# studna.net
KiCad netlist of a schematic drawn in EAGLE
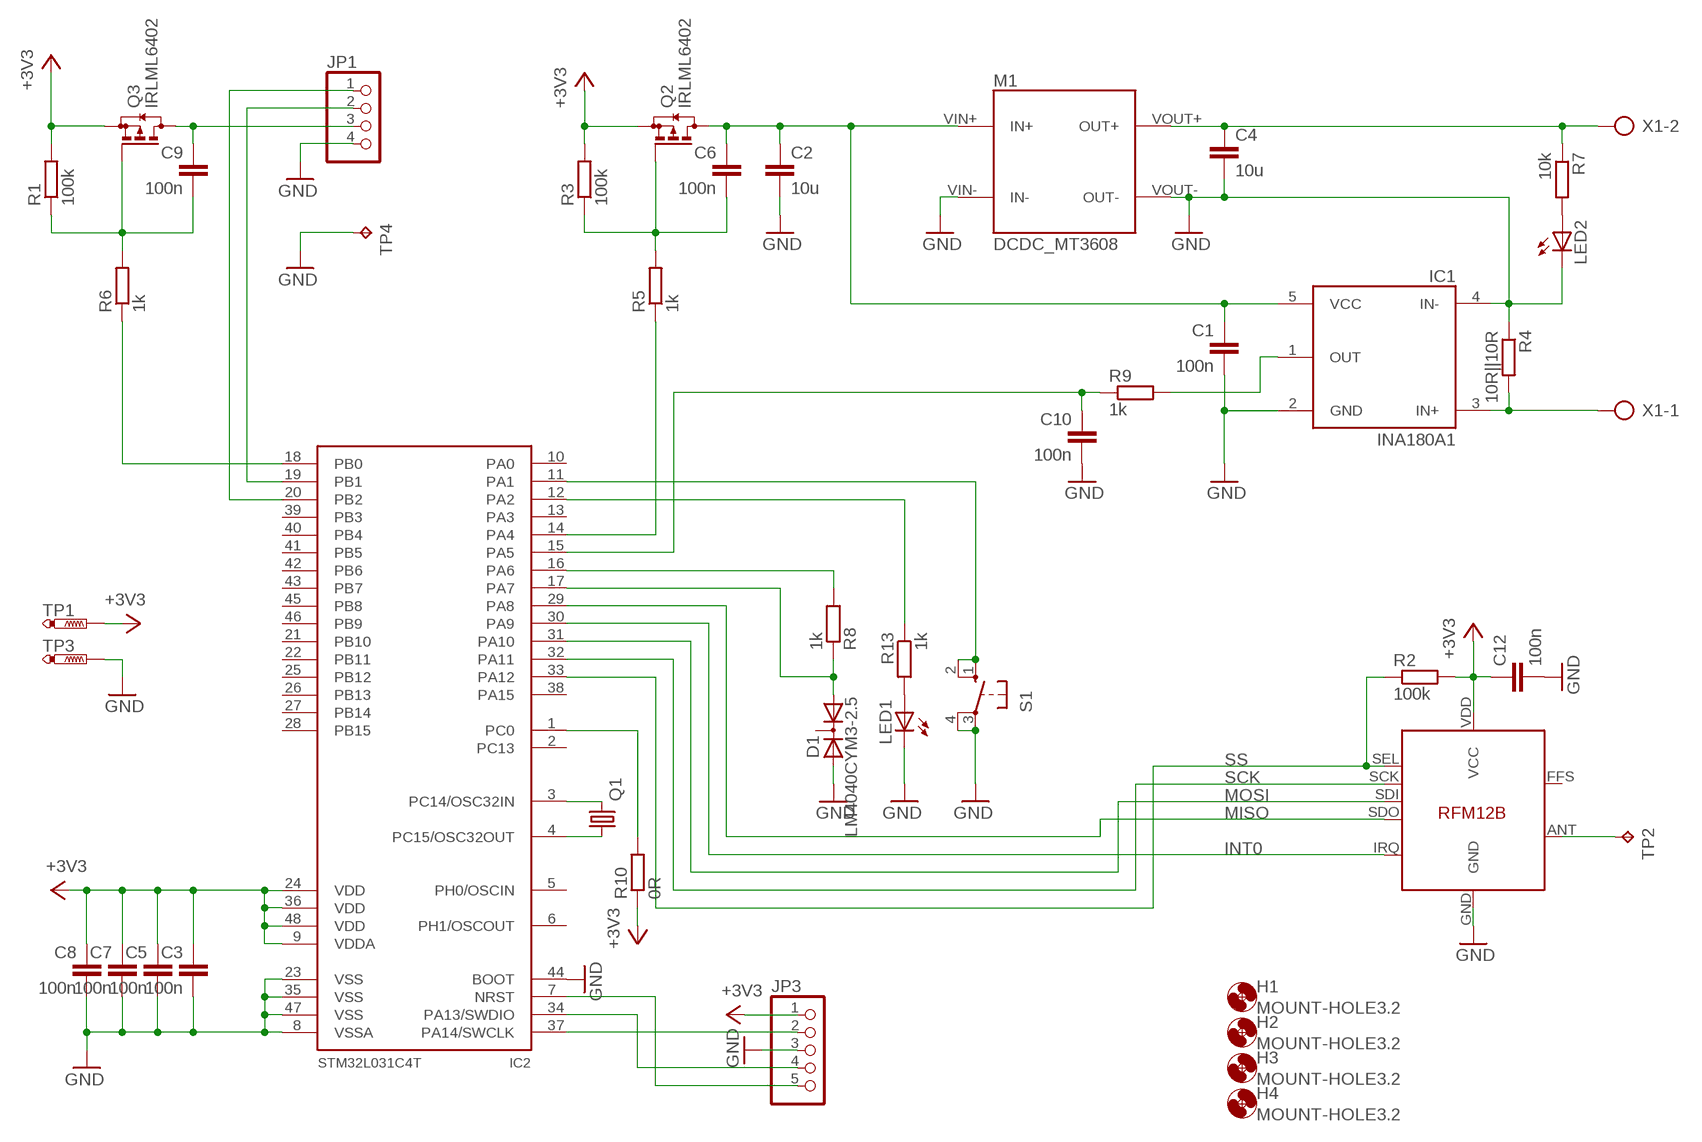
[diagram p0: schematic, sheet 1]

(export (version "E")
  (design (tool "Eeschema 10.0.6"))
  (components
    (comp (ref "C1")
      (value "100n")
      (footprint "eagle-import:C0603")
      (libsource (lib "eagle-import") (part "C-EUC0603"))
    )
    (comp (ref "C2")
      (value "10u")
      (footprint "eagle-import:C1206K")
      (libsource (lib "eagle-import") (part "C-EUC1206K"))
    )
    (comp (ref "C3")
      (value "100n")
      (footprint "eagle-import:C0603")
      (libsource (lib "eagle-import") (part "C-EUC0603"))
    )
    (comp (ref "C4")
      (value "10u")
      (footprint "eagle-import:C1206K")
      (libsource (lib "eagle-import") (part "C-EUC1206K"))
    )
    (comp (ref "C5")
      (value "100n")
      (footprint "eagle-import:C0603")
      (libsource (lib "eagle-import") (part "C-EUC0603"))
    )
    (comp (ref "C6")
      (value "100n")
      (footprint "eagle-import:C0603")
      (libsource (lib "eagle-import") (part "C-EUC0603"))
    )
    (comp (ref "C7")
      (value "100n")
      (footprint "eagle-import:C0603")
      (libsource (lib "eagle-import") (part "C-EUC0603"))
    )
    (comp (ref "C8")
      (value "100n")
      (footprint "eagle-import:C0603")
      (libsource (lib "eagle-import") (part "C-EUC0603"))
    )
    (comp (ref "C9")
      (value "100n")
      (footprint "eagle-import:C0603")
      (libsource (lib "eagle-import") (part "C-EUC0603"))
    )
    (comp (ref "C10")
      (value "100n")
      (footprint "eagle-import:C0603")
      (libsource (lib "eagle-import") (part "C-EUC0603"))
    )
    (comp (ref "C12")
      (value "100n")
      (footprint "eagle-import:C0603")
      (libsource (lib "eagle-import") (part "C-EUC0603"))
    )
    (comp (ref "D1")
      (value "LM4040CYM3-2.5")
      (footprint "eagle-import:SOT23")
      (libsource (lib "eagle-import") (part "DIODE-2AC|CASOT23"))
    )
    (comp (ref "H1")
      (value "MOUNT-HOLE3.2")
      (footprint "eagle-import:3,2")
      (libsource (lib "eagle-import") (part "MOUNT-HOLE3.2"))
    )
    (comp (ref "H2")
      (value "MOUNT-HOLE3.2")
      (footprint "eagle-import:3,2")
      (libsource (lib "eagle-import") (part "MOUNT-HOLE3.2"))
    )
    (comp (ref "H3")
      (value "MOUNT-HOLE3.2")
      (footprint "eagle-import:3,2")
      (libsource (lib "eagle-import") (part "MOUNT-HOLE3.2"))
    )
    (comp (ref "H4")
      (value "MOUNT-HOLE3.2")
      (footprint "eagle-import:3,2")
      (libsource (lib "eagle-import") (part "MOUNT-HOLE3.2"))
    )
    (comp (ref "IC1")
      (value "INA180A1")
      (footprint "eagle-import:SOT23-5L")
      (libsource (lib "eagle-import") (part "INA180"))
    )
    (comp (ref "IC2")
      (value "STM32L031C4T")
      (footprint "eagle-import:LQFP48")
      (libsource (lib "eagle-import") (part "STM32L031C4T"))
    )
    (comp (ref "IC3")
      (value "RFM12B")
      (footprint "eagle-import:RFM12B")
      (libsource (lib "eagle-import") (part "RFM12B"))
    )
    (comp (ref "JP1")
      (value "PINHD-1X4")
      (footprint "eagle-import:1X04")
      (libsource (lib "eagle-import") (part "PINHD-1X4"))
    )
    (comp (ref "JP3")
      (value "PINHD-1X5")
      (footprint "eagle-import:1X05")
      (libsource (lib "eagle-import") (part "PINHD-1X5"))
    )
    (comp (ref "LED1")
      (value "LED3MM")
      (footprint "eagle-import:LED3MM")
      (libsource (lib "eagle-import") (part "LED3MM"))
    )
    (comp (ref "LED2")
      (value "LED3MM")
      (footprint "eagle-import:LED3MM")
      (libsource (lib "eagle-import") (part "LED3MM"))
    )
    (comp (ref "M1")
      (value "DCDC_MT3608")
      (footprint "eagle-import:DCDC_MT3608")
      (libsource (lib "eagle-import") (part "DCDC_MT3608"))
    )
    (comp (ref "Q1")
      (value "CRYSTALTC38H")
      (footprint "eagle-import:TC38H")
      (libsource (lib "eagle-import") (part "CRYSTALTC38H"))
    )
    (comp (ref "Q2")
      (value "IRLML6402")
      (footprint "eagle-import:SOT23")
      (libsource (lib "eagle-import") (part "BSS84"))
    )
    (comp (ref "Q3")
      (value "IRLML6402")
      (footprint "eagle-import:SOT23")
      (libsource (lib "eagle-import") (part "BSS84"))
    )
    (comp (ref "R1")
      (value "100k")
      (footprint "eagle-import:R0603")
      (libsource (lib "eagle-import") (part "R-EU_R0603"))
    )
    (comp (ref "R2")
      (value "100k")
      (footprint "eagle-import:R0603")
      (libsource (lib "eagle-import") (part "R-EU_R0603"))
    )
    (comp (ref "R3")
      (value "100k")
      (footprint "eagle-import:R0603")
      (libsource (lib "eagle-import") (part "R-EU_R0603"))
    )
    (comp (ref "R4")
      (value "10R||10R")
      (footprint "eagle-import:R1206")
      (libsource (lib "eagle-import") (part "R-EU_R1206"))
    )
    (comp (ref "R5")
      (value "1k")
      (footprint "eagle-import:R0603")
      (libsource (lib "eagle-import") (part "R-EU_R0603"))
    )
    (comp (ref "R6")
      (value "1k")
      (footprint "eagle-import:R0603")
      (libsource (lib "eagle-import") (part "R-EU_R0603"))
    )
    (comp (ref "R7")
      (value "10k")
      (footprint "eagle-import:R0603")
      (libsource (lib "eagle-import") (part "R-EU_R0603"))
    )
    (comp (ref "R8")
      (value "1k")
      (footprint "eagle-import:R0603")
      (libsource (lib "eagle-import") (part "R-EU_R0603"))
    )
    (comp (ref "R9")
      (value "1k")
      (footprint "eagle-import:R0603")
      (libsource (lib "eagle-import") (part "R-EU_R0603"))
    )
    (comp (ref "R10")
      (value "0R")
      (footprint "eagle-import:R0603")
      (libsource (lib "eagle-import") (part "R-EU_R0603"))
    )
    (comp (ref "R13")
      (value "1k")
      (footprint "eagle-import:R0603")
      (libsource (lib "eagle-import") (part "R-EU_R0603"))
    )
    (comp (ref "S1")
      (value "10-XX")
      (footprint "eagle-import:B3F-10XX")
      (fields (field (name "MPN") "B3F-1000"))
      (libsource (lib "eagle-import") (part "10-XX"))
    )
    (comp (ref "TP1")
      (value "PTR1PAD1-17Y")
      (footprint "eagle-import:P1-17Y")
      (libsource (lib "eagle-import") (part "PTR1PAD1-17Y"))
    )
    (comp (ref "TP2")
      (value "TPB2,54")
      (footprint "eagle-import:B2,54")
      (libsource (lib "eagle-import") (part "TPB2,54"))
    )
    (comp (ref "TP3")
      (value "PTR1PAD1-17Y")
      (footprint "eagle-import:P1-17Y")
      (libsource (lib "eagle-import") (part "PTR1PAD1-17Y"))
    )
    (comp (ref "TP4")
      (value "TPPAD1-13Y")
      (footprint "eagle-import:P1-13Y")
      (libsource (lib "eagle-import") (part "TPPAD1-13Y"))
    )
    (comp (ref "X1")
      (value "AK500/2")
      (footprint "eagle-import:AK500_2")
      (libsource (lib "eagle-import") (part "AK500/2"))
    )
  )
  (nets
    (net (code "1") (name "+3V3") (class "Default")
      (node (ref "C12") (pin "1") (pinfunction "1_1") (pintype "passive"))
      (node (ref "C3") (pin "1") (pinfunction "1_1") (pintype "passive"))
      (node (ref "C5") (pin "1") (pinfunction "1_1") (pintype "passive"))
      (node (ref "C7") (pin "1") (pinfunction "1_1") (pintype "passive"))
      (node (ref "C8") (pin "1") (pinfunction "1_1") (pintype "passive"))
      (node (ref "IC2") (pin "24") (pinfunction "VDD_24") (pintype "power_in"))
      (node (ref "IC2") (pin "36") (pinfunction "VDD_36") (pintype "power_in"))
      (node (ref "IC2") (pin "48") (pinfunction "VDD_48") (pintype "power_in"))
      (node (ref "IC2") (pin "9") (pinfunction "VDDA_9") (pintype "power_in"))
      (node (ref "IC3") (pin "VDD") (pinfunction "VCC_VDD") (pintype "power_in"))
      (node (ref "JP3") (pin "1") (pinfunction "1_1") (pintype "passive"))
      (node (ref "Q2") (pin "2") (pinfunction "S_2") (pintype "passive"))
      (node (ref "Q3") (pin "2") (pinfunction "S_2") (pintype "passive"))
      (node (ref "R1") (pin "2") (pinfunction "2_2") (pintype "passive"))
      (node (ref "R10") (pin "1") (pinfunction "1_1") (pintype "passive"))
      (node (ref "R2") (pin "2") (pinfunction "2_2") (pintype "passive"))
      (node (ref "R3") (pin "2") (pinfunction "2_2") (pintype "passive"))
      (node (ref "TP1") (pin "TP") (pinfunction "TP_TP") (pintype "input"))
    )
    (net (code "2") (name "/INT0") (class "Default")
      (node (ref "IC2") (pin "30") (pinfunction "PA9_30") (pintype "bidirectional"))
      (node (ref "IC3") (pin "IRQ") (pinfunction "IRQ_IRQ") (pintype "open_collector"))
    )
    (net (code "3") (name "/MISO") (class "Default")
      (node (ref "IC2") (pin "29") (pinfunction "PA8_29") (pintype "bidirectional"))
      (node (ref "IC3") (pin "SDO") (pinfunction "SDO_SDO") (pintype "output"))
    )
    (net (code "4") (name "/MOSI") (class "Default")
      (node (ref "IC2") (pin "31") (pinfunction "PA10_31") (pintype "bidirectional"))
      (node (ref "IC3") (pin "SDI") (pinfunction "SDI_SDI") (pintype "input"))
    )
    (net (code "5") (name "/SCK") (class "Default")
      (node (ref "IC2") (pin "32") (pinfunction "PA11_32") (pintype "bidirectional"))
      (node (ref "IC3") (pin "SCK") (pinfunction "SCK_SCK") (pintype "input"))
    )
    (net (code "6") (name "/SS") (class "Default")
      (node (ref "IC2") (pin "33") (pinfunction "PA12_33") (pintype "bidirectional"))
      (node (ref "IC3") (pin "SEL") (pinfunction "SEL_SEL") (pintype "input"))
      (node (ref "R2") (pin "1") (pinfunction "1_1") (pintype "passive"))
    )
    (net (code "7") (name "GND") (class "Default")
      (node (ref "C1") (pin "2") (pinfunction "2_2") (pintype "passive"))
      (node (ref "C10") (pin "2") (pinfunction "2_2") (pintype "passive"))
      (node (ref "C12") (pin "2") (pinfunction "2_2") (pintype "passive"))
      (node (ref "C2") (pin "2") (pinfunction "2_2") (pintype "passive"))
      (node (ref "C3") (pin "2") (pinfunction "2_2") (pintype "passive"))
      (node (ref "C4") (pin "2") (pinfunction "2_2") (pintype "passive"))
      (node (ref "C5") (pin "2") (pinfunction "2_2") (pintype "passive"))
      (node (ref "C7") (pin "2") (pinfunction "2_2") (pintype "passive"))
      (node (ref "C8") (pin "2") (pinfunction "2_2") (pintype "passive"))
      (node (ref "D1") (pin "2") (pinfunction "A2_2") (pintype "passive"))
      (node (ref "IC1") (pin "2") (pinfunction "GND_2") (pintype "power_in"))
      (node (ref "IC1") (pin "4") (pinfunction "IN-_4") (pintype "passive"))
      (node (ref "IC2") (pin "23") (pinfunction "VSS_23") (pintype "power_in"))
      (node (ref "IC2") (pin "35") (pinfunction "VSS_35") (pintype "power_in"))
      (node (ref "IC2") (pin "44") (pinfunction "BOOT_44") (pintype "bidirectional"))
      (node (ref "IC2") (pin "47") (pinfunction "VSS_47") (pintype "power_in"))
      (node (ref "IC2") (pin "8") (pinfunction "VSSA_8") (pintype "power_in"))
      (node (ref "IC3") (pin "GND") (pinfunction "GND_GND") (pintype "power_in"))
      (node (ref "JP1") (pin "4") (pinfunction "4_4") (pintype "passive"))
      (node (ref "JP3") (pin "3") (pinfunction "3_3") (pintype "passive"))
      (node (ref "LED1") (pin "K") (pinfunction "C_K") (pintype "passive"))
      (node (ref "LED2") (pin "K") (pinfunction "C_K") (pintype "passive"))
      (node (ref "M1") (pin "VIN-") (pinfunction "IN-_VIN-") (pintype "passive"))
      (node (ref "M1") (pin "VOUT-") (pinfunction "OUT-_VOUT-") (pintype "passive"))
      (node (ref "R4") (pin "1") (pinfunction "1_1") (pintype "passive"))
      (node (ref "S1") (pin "3") (pinfunction "P_3") (pintype "passive"))
      (node (ref "S1") (pin "4") (pinfunction "P1_4") (pintype "passive"))
      (node (ref "TP3") (pin "TP") (pinfunction "TP_TP") (pintype "input"))
      (node (ref "TP4") (pin "TP") (pinfunction "TP_TP") (pintype "input"))
    )
    (net (code "8") (name "Net-(D1-A1)") (class "Default")
      (node (ref "D1") (pin "1") (pinfunction "A1_1") (pintype "passive"))
      (node (ref "IC2") (pin "17") (pinfunction "PA7_17") (pintype "bidirectional"))
      (node (ref "R8") (pin "1") (pinfunction "1_1") (pintype "passive"))
    )
    (net (code "9") (name "Net-(IC1-IN+)") (class "Default")
      (node (ref "IC1") (pin "3") (pinfunction "IN+_3") (pintype "passive"))
      (node (ref "R4") (pin "2") (pinfunction "2_2") (pintype "passive"))
      (node (ref "X1") (pin "1") (pinfunction "KL_1") (pintype "passive"))
    )
    (net (code "10") (name "Net-(IC1-OUT)") (class "Default")
      (node (ref "IC1") (pin "1") (pinfunction "OUT_1") (pintype "output"))
      (node (ref "R9") (pin "2") (pinfunction "2_2") (pintype "passive"))
    )
    (net (code "11") (name "Net-(IC1-VCC)") (class "Default")
      (node (ref "C1") (pin "1") (pinfunction "1_1") (pintype "passive"))
      (node (ref "C2") (pin "1") (pinfunction "1_1") (pintype "passive"))
      (node (ref "C6") (pin "1") (pinfunction "1_1") (pintype "passive"))
      (node (ref "IC1") (pin "5") (pinfunction "VCC_5") (pintype "power_in"))
      (node (ref "M1") (pin "VIN+") (pinfunction "IN+_VIN+") (pintype "passive"))
      (node (ref "Q2") (pin "3") (pinfunction "D_3") (pintype "passive"))
    )
    (net (code "12") (name "Net-(IC2-NRST)") (class "Default")
      (node (ref "IC2") (pin "7") (pinfunction "NRST_7") (pintype "bidirectional"))
      (node (ref "JP3") (pin "5") (pinfunction "5_5") (pintype "passive"))
    )
    (net (code "13") (name "Net-(IC2-PA1)") (class "Default")
      (node (ref "IC2") (pin "11") (pinfunction "PA1_11") (pintype "bidirectional"))
      (node (ref "S1") (pin "1") (pinfunction "S_1") (pintype "passive"))
      (node (ref "S1") (pin "2") (pinfunction "S1_2") (pintype "passive"))
    )
    (net (code "14") (name "Net-(IC2-PA2)") (class "Default")
      (node (ref "IC2") (pin "12") (pinfunction "PA2_12") (pintype "bidirectional"))
      (node (ref "R13") (pin "1") (pinfunction "1_1") (pintype "passive"))
    )
    (net (code "15") (name "Net-(IC2-PA4)") (class "Default")
      (node (ref "IC2") (pin "14") (pinfunction "PA4_14") (pintype "bidirectional"))
      (node (ref "R5") (pin "1") (pinfunction "1_1") (pintype "passive"))
    )
    (net (code "16") (name "Net-(IC2-PA5)") (class "Default")
      (node (ref "C10") (pin "1") (pinfunction "1_1") (pintype "passive"))
      (node (ref "IC2") (pin "15") (pinfunction "PA5_15") (pintype "bidirectional"))
      (node (ref "R9") (pin "1") (pinfunction "1_1") (pintype "passive"))
    )
    (net (code "17") (name "Net-(IC2-PA6)") (class "Default")
      (node (ref "IC2") (pin "16") (pinfunction "PA6_16") (pintype "bidirectional"))
      (node (ref "R8") (pin "2") (pinfunction "2_2") (pintype "passive"))
    )
    (net (code "18") (name "Net-(IC2-PA13{slash}SWDIO)") (class "Default")
      (node (ref "IC2") (pin "34") (pinfunction "PA13/SWDIO_34") (pintype "bidirectional"))
      (node (ref "JP3") (pin "4") (pinfunction "4_4") (pintype "passive"))
    )
    (net (code "19") (name "Net-(IC2-PA14{slash}SWCLK)") (class "Default")
      (node (ref "IC2") (pin "37") (pinfunction "PA14/SWCLK_37") (pintype "bidirectional"))
      (node (ref "JP3") (pin "2") (pinfunction "2_2") (pintype "passive"))
    )
    (net (code "20") (name "Net-(IC2-PB0)") (class "Default")
      (node (ref "IC2") (pin "18") (pinfunction "PB0_18") (pintype "bidirectional"))
      (node (ref "R6") (pin "1") (pinfunction "1_1") (pintype "passive"))
    )
    (net (code "21") (name "Net-(IC2-PB1)") (class "Default")
      (node (ref "IC2") (pin "19") (pinfunction "PB1_19") (pintype "bidirectional"))
      (node (ref "JP1") (pin "2") (pinfunction "2_2") (pintype "passive"))
    )
    (net (code "22") (name "Net-(IC2-PB2)") (class "Default")
      (node (ref "IC2") (pin "20") (pinfunction "PB2_20") (pintype "bidirectional"))
      (node (ref "JP1") (pin "1") (pinfunction "1_1") (pintype "passive"))
    )
    (net (code "23") (name "Net-(IC2-PC0)") (class "Default")
      (node (ref "IC2") (pin "1") (pinfunction "PC0_1") (pintype "bidirectional"))
      (node (ref "R10") (pin "2") (pinfunction "2_2") (pintype "passive"))
    )
    (net (code "24") (name "Net-(IC2-PC14{slash}OSC32IN)") (class "Default")
      (node (ref "IC2") (pin "3") (pinfunction "PC14/OSC32IN_3") (pintype "passive"))
      (node (ref "Q1") (pin "2") (pinfunction "2_2") (pintype "passive"))
    )
    (net (code "25") (name "Net-(IC2-PC15{slash}OSC32OUT)") (class "Default")
      (node (ref "IC2") (pin "4") (pinfunction "PC15/OSC32OUT_4") (pintype "passive"))
      (node (ref "Q1") (pin "1") (pinfunction "1_1") (pintype "passive"))
    )
    (net (code "26") (name "Net-(IC3-PadANT)") (class "Default")
      (node (ref "IC3") (pin "ANT") (pinfunction "ANT_ANT") (pintype "passive"))
      (node (ref "TP2") (pin "TP") (pinfunction "TP_TP") (pintype "input"))
    )
    (net (code "27") (name "Net-(LED1-PadA)") (class "Default")
      (node (ref "LED1") (pin "A") (pinfunction "A_A") (pintype "passive"))
      (node (ref "R13") (pin "2") (pinfunction "2_2") (pintype "passive"))
    )
    (net (code "28") (name "Net-(LED2-PadA)") (class "Default")
      (node (ref "LED2") (pin "A") (pinfunction "A_A") (pintype "passive"))
      (node (ref "R7") (pin "2") (pinfunction "2_2") (pintype "passive"))
    )
    (net (code "29") (name "Net-(M1-OUT+)") (class "Default")
      (node (ref "C4") (pin "1") (pinfunction "1_1") (pintype "passive"))
      (node (ref "M1") (pin "VOUT+") (pinfunction "OUT+_VOUT+") (pintype "passive"))
      (node (ref "R7") (pin "1") (pinfunction "1_1") (pintype "passive"))
      (node (ref "X1") (pin "2") (pinfunction "KL_2") (pintype "passive"))
    )
    (net (code "30") (name "Net-(Q2-G)") (class "Default")
      (node (ref "C6") (pin "2") (pinfunction "2_2") (pintype "passive"))
      (node (ref "Q2") (pin "1") (pinfunction "G_1") (pintype "passive"))
      (node (ref "R3") (pin "1") (pinfunction "1_1") (pintype "passive"))
      (node (ref "R5") (pin "2") (pinfunction "2_2") (pintype "passive"))
    )
    (net (code "31") (name "Net-(Q3-D)") (class "Default")
      (node (ref "C9") (pin "1") (pinfunction "1_1") (pintype "passive"))
      (node (ref "JP1") (pin "3") (pinfunction "3_3") (pintype "passive"))
      (node (ref "Q3") (pin "3") (pinfunction "D_3") (pintype "passive"))
    )
    (net (code "32") (name "Net-(Q3-G)") (class "Default")
      (node (ref "C9") (pin "2") (pinfunction "2_2") (pintype "passive"))
      (node (ref "Q3") (pin "1") (pinfunction "G_1") (pintype "passive"))
      (node (ref "R1") (pin "1") (pinfunction "1_1") (pintype "passive"))
      (node (ref "R6") (pin "2") (pinfunction "2_2") (pintype "passive"))
    )
    (net (code "33") (name "unconnected-(D1-C-Pad3)") (class "Default")
      (node (ref "D1") (pin "3") (pinfunction "C_3") (pintype "passive"))
    )
    (net (code "34") (name "unconnected-(IC2-PA0-Pad10)") (class "Default")
      (node (ref "IC2") (pin "10") (pinfunction "PA0_10") (pintype "bidirectional"))
    )
    (net (code "35") (name "unconnected-(IC2-PA3-Pad13)") (class "Default")
      (node (ref "IC2") (pin "13") (pinfunction "PA3_13") (pintype "bidirectional"))
    )
    (net (code "36") (name "unconnected-(IC2-PA15-Pad38)") (class "Default")
      (node (ref "IC2") (pin "38") (pinfunction "PA15_38") (pintype "bidirectional"))
    )
    (net (code "37") (name "unconnected-(IC2-PB3-Pad39)") (class "Default")
      (node (ref "IC2") (pin "39") (pinfunction "PB3_39") (pintype "bidirectional"))
    )
    (net (code "38") (name "unconnected-(IC2-PB4-Pad40)") (class "Default")
      (node (ref "IC2") (pin "40") (pinfunction "PB4_40") (pintype "bidirectional"))
    )
    (net (code "39") (name "unconnected-(IC2-PB5-Pad41)") (class "Default")
      (node (ref "IC2") (pin "41") (pinfunction "PB5_41") (pintype "bidirectional"))
    )
    (net (code "40") (name "unconnected-(IC2-PB6-Pad42)") (class "Default")
      (node (ref "IC2") (pin "42") (pinfunction "PB6_42") (pintype "bidirectional"))
    )
    (net (code "41") (name "unconnected-(IC2-PB7-Pad43)") (class "Default")
      (node (ref "IC2") (pin "43") (pinfunction "PB7_43") (pintype "bidirectional"))
    )
    (net (code "42") (name "unconnected-(IC2-PB8-Pad45)") (class "Default")
      (node (ref "IC2") (pin "45") (pinfunction "PB8_45") (pintype "bidirectional"))
    )
    (net (code "43") (name "unconnected-(IC2-PB9-Pad46)") (class "Default")
      (node (ref "IC2") (pin "46") (pinfunction "PB9_46") (pintype "bidirectional"))
    )
    (net (code "44") (name "unconnected-(IC2-PB10-Pad21)") (class "Default")
      (node (ref "IC2") (pin "21") (pinfunction "PB10_21") (pintype "bidirectional"))
    )
    (net (code "45") (name "unconnected-(IC2-PB11-Pad22)") (class "Default")
      (node (ref "IC2") (pin "22") (pinfunction "PB11_22") (pintype "bidirectional"))
    )
    (net (code "46") (name "unconnected-(IC2-PB12-Pad25)") (class "Default")
      (node (ref "IC2") (pin "25") (pinfunction "PB12_25") (pintype "bidirectional"))
    )
    (net (code "47") (name "unconnected-(IC2-PB13-Pad26)") (class "Default")
      (node (ref "IC2") (pin "26") (pinfunction "PB13_26") (pintype "bidirectional"))
    )
    (net (code "48") (name "unconnected-(IC2-PB14-Pad27)") (class "Default")
      (node (ref "IC2") (pin "27") (pinfunction "PB14_27") (pintype "bidirectional"))
    )
    (net (code "49") (name "unconnected-(IC2-PB15-Pad28)") (class "Default")
      (node (ref "IC2") (pin "28") (pinfunction "PB15_28") (pintype "bidirectional"))
    )
    (net (code "50") (name "unconnected-(IC2-PC13-Pad2)") (class "Default")
      (node (ref "IC2") (pin "2") (pinfunction "PC13_2") (pintype "bidirectional"))
    )
    (net (code "51") (name "unconnected-(IC2-PH0{slash}OSCIN-Pad5)") (class "Default")
      (node (ref "IC2") (pin "5") (pinfunction "PH0/OSCIN_5") (pintype "passive"))
    )
    (net (code "52") (name "unconnected-(IC2-PH1{slash}OSCOUT-Pad6)") (class "Default")
      (node (ref "IC2") (pin "6") (pinfunction "PH1/OSCOUT_6") (pintype "passive"))
    )
    (net (code "53") (name "unconnected-(IC3-PadFFS)") (class "Default")
      (node (ref "IC3") (pin "FFS") (pinfunction "FFS_FFS") (pintype "bidirectional"))
    )
  )
)
